# lf.net
KiCad netlist of a schematic drawn in EAGLE
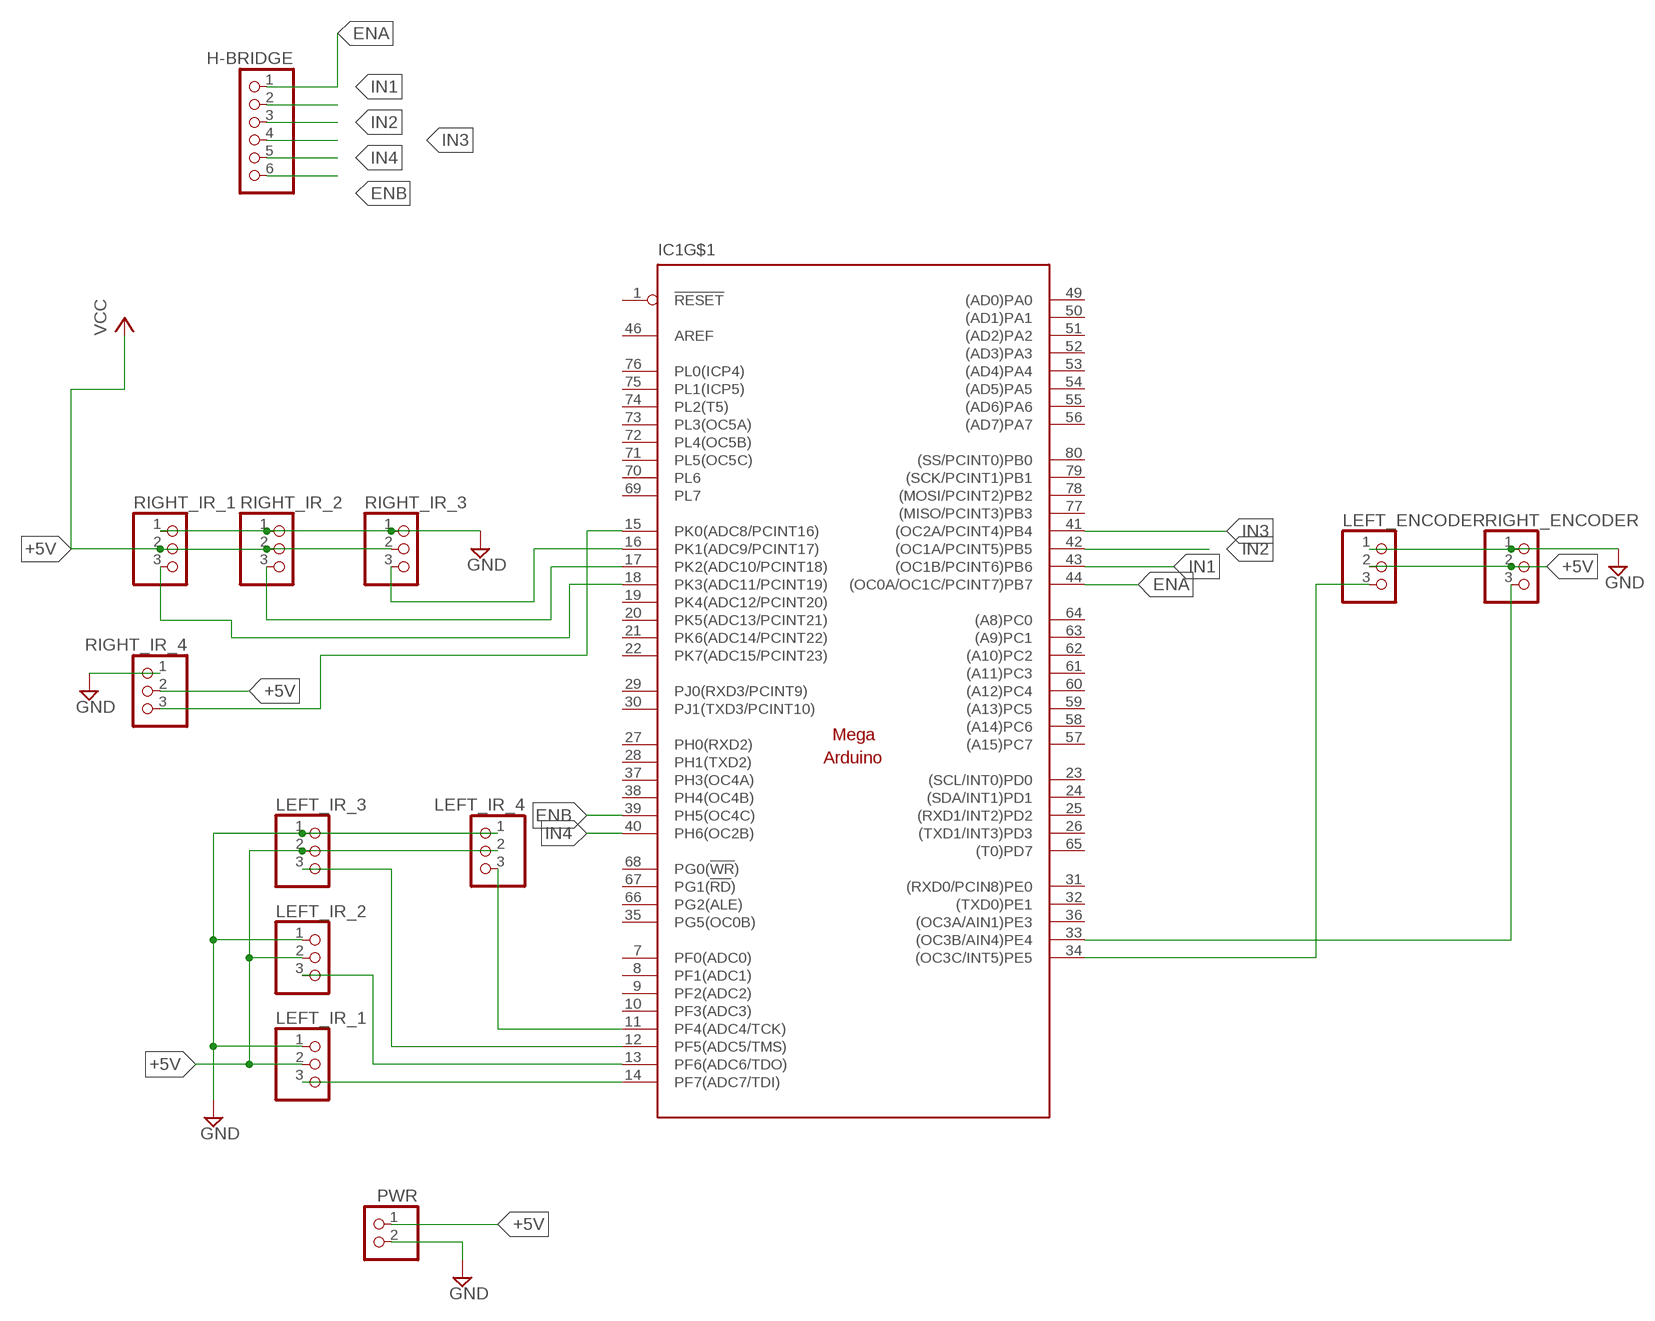
[diagram p0: schematic, sheet 1]

(export (version "E")
  (design (tool "Eeschema 10.0.6"))
  (components
    (comp (ref "H-BRIDGE")
      (value "PINHD-1X6")
      (footprint "eagle-import:1X06")
      (libsource (lib "eagle-import") (part "PINHD-1X6"))
    )
    (comp (ref "IC1")
      (value "MEGAARDUINO_22")
      (footprint "eagle-import:MEGA_ARDUINO_2")
      (libsource (lib "eagle-import") (part "MEGAARDUINO_22"))
    )
    (comp (ref "LEFT_ENCODER")
      (value "PINHD-1X3")
      (footprint "eagle-import:1X03")
      (libsource (lib "eagle-import") (part "PINHD-1X3"))
    )
    (comp (ref "LEFT_IR_1")
      (value "PINHD-1X3")
      (footprint "eagle-import:1X03")
      (libsource (lib "eagle-import") (part "PINHD-1X3"))
    )
    (comp (ref "LEFT_IR_2")
      (value "PINHD-1X3")
      (footprint "eagle-import:1X03")
      (libsource (lib "eagle-import") (part "PINHD-1X3"))
    )
    (comp (ref "LEFT_IR_3")
      (value "PINHD-1X3")
      (footprint "eagle-import:1X03")
      (libsource (lib "eagle-import") (part "PINHD-1X3"))
    )
    (comp (ref "LEFT_IR_4")
      (value "PINHD-1X3")
      (footprint "eagle-import:1X03")
      (libsource (lib "eagle-import") (part "PINHD-1X3"))
    )
    (comp (ref "PWR")
      (value "PINHD-1X2")
      (footprint "eagle-import:1X02")
      (libsource (lib "eagle-import") (part "PINHD-1X2"))
    )
    (comp (ref "RIGHT_ENCODER")
      (value "PINHD-1X3")
      (footprint "eagle-import:1X03")
      (libsource (lib "eagle-import") (part "PINHD-1X3"))
    )
    (comp (ref "RIGHT_IR_1")
      (value "PINHD-1X3")
      (footprint "eagle-import:1X03")
      (libsource (lib "eagle-import") (part "PINHD-1X3"))
    )
    (comp (ref "RIGHT_IR_2")
      (value "PINHD-1X3")
      (footprint "eagle-import:1X03")
      (libsource (lib "eagle-import") (part "PINHD-1X3"))
    )
    (comp (ref "RIGHT_IR_3")
      (value "PINHD-1X3")
      (footprint "eagle-import:1X03")
      (libsource (lib "eagle-import") (part "PINHD-1X3"))
    )
    (comp (ref "RIGHT_IR_4")
      (value "PINHD-1X3")
      (footprint "eagle-import:1X03")
      (libsource (lib "eagle-import") (part "PINHD-1X3"))
    )
  )
  (nets
    (net (code "1") (name "+5V") (class "Default")
      (node (ref "LEFT_ENCODER") (pin "2") (pinfunction "2_2") (pintype "passive"))
      (node (ref "LEFT_IR_1") (pin "2") (pinfunction "2_2") (pintype "passive"))
      (node (ref "LEFT_IR_2") (pin "2") (pinfunction "2_2") (pintype "passive"))
      (node (ref "LEFT_IR_3") (pin "2") (pinfunction "2_2") (pintype "passive"))
      (node (ref "LEFT_IR_4") (pin "2") (pinfunction "2_2") (pintype "passive"))
      (node (ref "PWR") (pin "1") (pinfunction "1_1") (pintype "passive"))
      (node (ref "RIGHT_ENCODER") (pin "2") (pinfunction "2_2") (pintype "passive"))
      (node (ref "RIGHT_IR_1") (pin "2") (pinfunction "2_2") (pintype "passive"))
      (node (ref "RIGHT_IR_2") (pin "2") (pinfunction "2_2") (pintype "passive"))
      (node (ref "RIGHT_IR_3") (pin "2") (pinfunction "2_2") (pintype "passive"))
      (node (ref "RIGHT_IR_4") (pin "2") (pinfunction "2_2") (pintype "passive"))
    )
    (net (code "2") (name "ENA") (class "Default")
      (node (ref "H-BRIDGE") (pin "1") (pinfunction "1_1") (pintype "passive"))
      (node (ref "IC1") (pin "44") (pinfunction "(OC0A/OC1C/PCINT7)PB7_44") (pintype "bidirectional"))
    )
    (net (code "3") (name "ENB") (class "Default")
      (node (ref "H-BRIDGE") (pin "6") (pinfunction "6_6") (pintype "passive"))
      (node (ref "IC1") (pin "39") (pinfunction "PH5(OC4C)_39") (pintype "bidirectional"))
    )
    (net (code "4") (name "GND") (class "Default")
      (node (ref "LEFT_ENCODER") (pin "1") (pinfunction "1_1") (pintype "passive"))
      (node (ref "LEFT_IR_1") (pin "1") (pinfunction "1_1") (pintype "passive"))
      (node (ref "LEFT_IR_2") (pin "1") (pinfunction "1_1") (pintype "passive"))
      (node (ref "LEFT_IR_3") (pin "1") (pinfunction "1_1") (pintype "passive"))
      (node (ref "LEFT_IR_4") (pin "1") (pinfunction "1_1") (pintype "passive"))
      (node (ref "PWR") (pin "2") (pinfunction "2_2") (pintype "passive"))
      (node (ref "RIGHT_ENCODER") (pin "1") (pinfunction "1_1") (pintype "passive"))
      (node (ref "RIGHT_IR_1") (pin "1") (pinfunction "1_1") (pintype "passive"))
      (node (ref "RIGHT_IR_2") (pin "1") (pinfunction "1_1") (pintype "passive"))
      (node (ref "RIGHT_IR_3") (pin "1") (pinfunction "1_1") (pintype "passive"))
      (node (ref "RIGHT_IR_4") (pin "1") (pinfunction "1_1") (pintype "passive"))
    )
    (net (code "5") (name "IN1") (class "Default")
      (node (ref "H-BRIDGE") (pin "2") (pinfunction "2_2") (pintype "passive"))
      (node (ref "IC1") (pin "43") (pinfunction "(OC1B/PCINT6)PB6_43") (pintype "bidirectional"))
    )
    (net (code "6") (name "IN2") (class "Default")
      (node (ref "H-BRIDGE") (pin "3") (pinfunction "3_3") (pintype "passive"))
      (node (ref "IC1") (pin "42") (pinfunction "(OC1A/PCINT5)PB5_42") (pintype "bidirectional"))
    )
    (net (code "7") (name "IN3") (class "Default")
      (node (ref "H-BRIDGE") (pin "4") (pinfunction "4_4") (pintype "passive"))
      (node (ref "IC1") (pin "41") (pinfunction "(OC2A/PCINT4)PB4_41") (pintype "bidirectional"))
    )
    (net (code "8") (name "IN4") (class "Default")
      (node (ref "H-BRIDGE") (pin "5") (pinfunction "5_5") (pintype "passive"))
      (node (ref "IC1") (pin "40") (pinfunction "PH6(OC2B)_40") (pintype "bidirectional"))
    )
    (net (code "9") (name "Net-(IC1A-(OC3B{slash}AIN4)PE4)") (class "Default")
      (node (ref "IC1") (pin "33") (pinfunction "(OC3B/AIN4)PE4_33") (pintype "bidirectional"))
      (node (ref "RIGHT_ENCODER") (pin "3") (pinfunction "3_3") (pintype "passive"))
    )
    (net (code "10") (name "Net-(IC1A-(OC3C{slash}INT5)PE5)") (class "Default")
      (node (ref "IC1") (pin "34") (pinfunction "(OC3C/INT5)PE5_34") (pintype "bidirectional"))
      (node (ref "LEFT_ENCODER") (pin "3") (pinfunction "3_3") (pintype "passive"))
    )
    (net (code "11") (name "Net-(IC1A-PF4(ADC4{slash}TCK))") (class "Default")
      (node (ref "IC1") (pin "11") (pinfunction "PF4(ADC4/TCK)_11") (pintype "bidirectional"))
      (node (ref "LEFT_IR_4") (pin "3") (pinfunction "3_3") (pintype "passive"))
    )
    (net (code "12") (name "Net-(IC1A-PF5(ADC5{slash}TMS))") (class "Default")
      (node (ref "IC1") (pin "12") (pinfunction "PF5(ADC5/TMS)_12") (pintype "bidirectional"))
      (node (ref "LEFT_IR_3") (pin "3") (pinfunction "3_3") (pintype "passive"))
    )
    (net (code "13") (name "Net-(IC1A-PF6(ADC6{slash}TDO))") (class "Default")
      (node (ref "IC1") (pin "13") (pinfunction "PF6(ADC6/TDO)_13") (pintype "bidirectional"))
      (node (ref "LEFT_IR_2") (pin "3") (pinfunction "3_3") (pintype "passive"))
    )
    (net (code "14") (name "Net-(IC1A-PF7(ADC7{slash}TDI))") (class "Default")
      (node (ref "IC1") (pin "14") (pinfunction "PF7(ADC7/TDI)_14") (pintype "bidirectional"))
      (node (ref "LEFT_IR_1") (pin "3") (pinfunction "3_3") (pintype "passive"))
    )
    (net (code "15") (name "Net-(IC1A-PK0(ADC8{slash}PCINT16))") (class "Default")
      (node (ref "IC1") (pin "15") (pinfunction "PK0(ADC8/PCINT16)_15") (pintype "bidirectional"))
      (node (ref "RIGHT_IR_4") (pin "3") (pinfunction "3_3") (pintype "passive"))
    )
    (net (code "16") (name "Net-(IC1A-PK1(ADC9{slash}PCINT17))") (class "Default")
      (node (ref "IC1") (pin "16") (pinfunction "PK1(ADC9/PCINT17)_16") (pintype "bidirectional"))
      (node (ref "RIGHT_IR_3") (pin "3") (pinfunction "3_3") (pintype "passive"))
    )
    (net (code "17") (name "Net-(IC1A-PK2(ADC10{slash}PCINT18))") (class "Default")
      (node (ref "IC1") (pin "17") (pinfunction "PK2(ADC10/PCINT18)_17") (pintype "bidirectional"))
      (node (ref "RIGHT_IR_2") (pin "3") (pinfunction "3_3") (pintype "passive"))
    )
    (net (code "18") (name "Net-(IC1A-PK3(ADC11{slash}PCINT19))") (class "Default")
      (node (ref "IC1") (pin "18") (pinfunction "PK3(ADC11/PCINT19)_18") (pintype "bidirectional"))
      (node (ref "RIGHT_IR_1") (pin "3") (pinfunction "3_3") (pintype "passive"))
    )
    (net (code "19") (name "unconnected-(IC1A-(A8)PC0-Pad64)") (class "Default")
      (node (ref "IC1") (pin "64") (pinfunction "(A8)PC0_64") (pintype "bidirectional"))
    )
    (net (code "20") (name "unconnected-(IC1A-(A9)PC1-Pad63)") (class "Default")
      (node (ref "IC1") (pin "63") (pinfunction "(A9)PC1_63") (pintype "bidirectional"))
    )
    (net (code "21") (name "unconnected-(IC1A-(A10)PC2-Pad62)") (class "Default")
      (node (ref "IC1") (pin "62") (pinfunction "(A10)PC2_62") (pintype "bidirectional"))
    )
    (net (code "22") (name "unconnected-(IC1A-(A11)PC3-Pad61)") (class "Default")
      (node (ref "IC1") (pin "61") (pinfunction "(A11)PC3_61") (pintype "bidirectional"))
    )
    (net (code "23") (name "unconnected-(IC1A-(A12)PC4-Pad60)") (class "Default")
      (node (ref "IC1") (pin "60") (pinfunction "(A12)PC4_60") (pintype "bidirectional"))
    )
    (net (code "24") (name "unconnected-(IC1A-(A13)PC5-Pad59)") (class "Default")
      (node (ref "IC1") (pin "59") (pinfunction "(A13)PC5_59") (pintype "bidirectional"))
    )
    (net (code "25") (name "unconnected-(IC1A-(A14)PC6-Pad58)") (class "Default")
      (node (ref "IC1") (pin "58") (pinfunction "(A14)PC6_58") (pintype "bidirectional"))
    )
    (net (code "26") (name "unconnected-(IC1A-(A15)PC7-Pad57)") (class "Default")
      (node (ref "IC1") (pin "57") (pinfunction "(A15)PC7_57") (pintype "bidirectional"))
    )
    (net (code "27") (name "unconnected-(IC1A-(AD0)PA0-Pad49)") (class "Default")
      (node (ref "IC1") (pin "49") (pinfunction "(AD0)PA0_49") (pintype "bidirectional"))
    )
    (net (code "28") (name "unconnected-(IC1A-(AD1)PA1-Pad50)") (class "Default")
      (node (ref "IC1") (pin "50") (pinfunction "(AD1)PA1_50") (pintype "bidirectional"))
    )
    (net (code "29") (name "unconnected-(IC1A-(AD2)PA2-Pad51)") (class "Default")
      (node (ref "IC1") (pin "51") (pinfunction "(AD2)PA2_51") (pintype "bidirectional"))
    )
    (net (code "30") (name "unconnected-(IC1A-(AD3)PA3-Pad52)") (class "Default")
      (node (ref "IC1") (pin "52") (pinfunction "(AD3)PA3_52") (pintype "bidirectional"))
    )
    (net (code "31") (name "unconnected-(IC1A-(AD4)PA4-Pad53)") (class "Default")
      (node (ref "IC1") (pin "53") (pinfunction "(AD4)PA4_53") (pintype "bidirectional"))
    )
    (net (code "32") (name "unconnected-(IC1A-(AD5)PA5-Pad54)") (class "Default")
      (node (ref "IC1") (pin "54") (pinfunction "(AD5)PA5_54") (pintype "bidirectional"))
    )
    (net (code "33") (name "unconnected-(IC1A-(AD6)PA6-Pad55)") (class "Default")
      (node (ref "IC1") (pin "55") (pinfunction "(AD6)PA6_55") (pintype "bidirectional"))
    )
    (net (code "34") (name "unconnected-(IC1A-(AD7)PA7-Pad56)") (class "Default")
      (node (ref "IC1") (pin "56") (pinfunction "(AD7)PA7_56") (pintype "bidirectional"))
    )
    (net (code "35") (name "unconnected-(IC1A-(MISO{slash}PCINT3)PB3-Pad77)") (class "Default")
      (node (ref "IC1") (pin "77") (pinfunction "(MISO/PCINT3)PB3_77") (pintype "bidirectional"))
    )
    (net (code "36") (name "unconnected-(IC1A-(MOSI{slash}PCINT2)PB2-Pad78)") (class "Default")
      (node (ref "IC1") (pin "78") (pinfunction "(MOSI/PCINT2)PB2_78") (pintype "bidirectional"))
    )
    (net (code "37") (name "unconnected-(IC1A-(OC3A{slash}AIN1)PE3-Pad36)") (class "Default")
      (node (ref "IC1") (pin "36") (pinfunction "(OC3A/AIN1)PE3_36") (pintype "bidirectional"))
    )
    (net (code "38") (name "unconnected-(IC1A-(RXD0{slash}PCIN8)PE0-Pad31)") (class "Default")
      (node (ref "IC1") (pin "31") (pinfunction "(RXD0/PCIN8)PE0_31") (pintype "bidirectional"))
    )
    (net (code "39") (name "unconnected-(IC1A-(RXD1{slash}INT2)PD2-Pad25)") (class "Default")
      (node (ref "IC1") (pin "25") (pinfunction "(RXD1/INT2)PD2_25") (pintype "bidirectional"))
    )
    (net (code "40") (name "unconnected-(IC1A-(SCK{slash}PCINT1)PB1-Pad79)") (class "Default")
      (node (ref "IC1") (pin "79") (pinfunction "(SCK/PCINT1)PB1_79") (pintype "bidirectional"))
    )
    (net (code "41") (name "unconnected-(IC1A-(SCL{slash}INT0)PD0-Pad23)") (class "Default")
      (node (ref "IC1") (pin "23") (pinfunction "(SCL/INT0)PD0_23") (pintype "bidirectional"))
    )
    (net (code "42") (name "unconnected-(IC1A-(SDA{slash}INT1)PD1-Pad24)") (class "Default")
      (node (ref "IC1") (pin "24") (pinfunction "(SDA/INT1)PD1_24") (pintype "bidirectional"))
    )
    (net (code "43") (name "unconnected-(IC1A-(SS{slash}PCINT0)PB0-Pad80)") (class "Default")
      (node (ref "IC1") (pin "80") (pinfunction "(SS/PCINT0)PB0_80") (pintype "bidirectional"))
    )
    (net (code "44") (name "unconnected-(IC1A-(T0)PD7-Pad65)") (class "Default")
      (node (ref "IC1") (pin "65") (pinfunction "(T0)PD7_65") (pintype "bidirectional"))
    )
    (net (code "45") (name "unconnected-(IC1A-(TXD0)PE1-Pad32)") (class "Default")
      (node (ref "IC1") (pin "32") (pinfunction "(TXD0)PE1_32") (pintype "bidirectional"))
    )
    (net (code "46") (name "unconnected-(IC1A-(TXD1{slash}INT3)PD3-Pad26)") (class "Default")
      (node (ref "IC1") (pin "26") (pinfunction "(TXD1/INT3)PD3_26") (pintype "bidirectional"))
    )
    (net (code "47") (name "unconnected-(IC1A-AREF-Pad46)") (class "Default")
      (node (ref "IC1") (pin "46") (pinfunction "AREF_46") (pintype "bidirectional"))
    )
    (net (code "48") (name "unconnected-(IC1A-PF0(ADC0)-Pad7)") (class "Default")
      (node (ref "IC1") (pin "7") (pinfunction "PF0(ADC0)_7") (pintype "bidirectional"))
    )
    (net (code "49") (name "unconnected-(IC1A-PF1(ADC1)-Pad8)") (class "Default")
      (node (ref "IC1") (pin "8") (pinfunction "PF1(ADC1)_8") (pintype "bidirectional"))
    )
    (net (code "50") (name "unconnected-(IC1A-PF2(ADC2)-Pad9)") (class "Default")
      (node (ref "IC1") (pin "9") (pinfunction "PF2(ADC2)_9") (pintype "bidirectional"))
    )
    (net (code "51") (name "unconnected-(IC1A-PF3(ADC3)-Pad10)") (class "Default")
      (node (ref "IC1") (pin "10") (pinfunction "PF3(ADC3)_10") (pintype "bidirectional"))
    )
    (net (code "52") (name "unconnected-(IC1A-PG0(~{WR})-Pad68)") (class "Default")
      (node (ref "IC1") (pin "68") (pinfunction "PG0(~{WR})_68") (pintype "bidirectional"))
    )
    (net (code "53") (name "unconnected-(IC1A-PG1(~{RD})-Pad67)") (class "Default")
      (node (ref "IC1") (pin "67") (pinfunction "PG1(~{RD})_67") (pintype "bidirectional"))
    )
    (net (code "54") (name "unconnected-(IC1A-PG2(ALE)-Pad66)") (class "Default")
      (node (ref "IC1") (pin "66") (pinfunction "PG2(ALE)_66") (pintype "bidirectional"))
    )
    (net (code "55") (name "unconnected-(IC1A-PG5(OC0B)-Pad35)") (class "Default")
      (node (ref "IC1") (pin "35") (pinfunction "PG5(OC0B)_35") (pintype "bidirectional"))
    )
    (net (code "56") (name "unconnected-(IC1A-PH0(RXD2)-Pad27)") (class "Default")
      (node (ref "IC1") (pin "27") (pinfunction "PH0(RXD2)_27") (pintype "bidirectional"))
    )
    (net (code "57") (name "unconnected-(IC1A-PH1(TXD2)-Pad28)") (class "Default")
      (node (ref "IC1") (pin "28") (pinfunction "PH1(TXD2)_28") (pintype "bidirectional"))
    )
    (net (code "58") (name "unconnected-(IC1A-PH3(OC4A)-Pad37)") (class "Default")
      (node (ref "IC1") (pin "37") (pinfunction "PH3(OC4A)_37") (pintype "bidirectional"))
    )
    (net (code "59") (name "unconnected-(IC1A-PH4(OC4B)-Pad38)") (class "Default")
      (node (ref "IC1") (pin "38") (pinfunction "PH4(OC4B)_38") (pintype "bidirectional"))
    )
    (net (code "60") (name "unconnected-(IC1A-PJ0(RXD3{slash}PCINT9)-Pad29)") (class "Default")
      (node (ref "IC1") (pin "29") (pinfunction "PJ0(RXD3/PCINT9)_29") (pintype "bidirectional"))
    )
    (net (code "61") (name "unconnected-(IC1A-PJ1(TXD3{slash}PCINT10)-Pad30)") (class "Default")
      (node (ref "IC1") (pin "30") (pinfunction "PJ1(TXD3/PCINT10)_30") (pintype "bidirectional"))
    )
    (net (code "62") (name "unconnected-(IC1A-PK4(ADC12{slash}PCINT20)-Pad19)") (class "Default")
      (node (ref "IC1") (pin "19") (pinfunction "PK4(ADC12/PCINT20)_19") (pintype "bidirectional"))
    )
    (net (code "63") (name "unconnected-(IC1A-PK5(ADC13{slash}PCINT21)-Pad20)") (class "Default")
      (node (ref "IC1") (pin "20") (pinfunction "PK5(ADC13/PCINT21)_20") (pintype "bidirectional"))
    )
    (net (code "64") (name "unconnected-(IC1A-PK6(ADC14{slash}PCINT22)-Pad21)") (class "Default")
      (node (ref "IC1") (pin "21") (pinfunction "PK6(ADC14/PCINT22)_21") (pintype "bidirectional"))
    )
    (net (code "65") (name "unconnected-(IC1A-PK7(ADC15{slash}PCINT23)-Pad22)") (class "Default")
      (node (ref "IC1") (pin "22") (pinfunction "PK7(ADC15/PCINT23)_22") (pintype "bidirectional"))
    )
    (net (code "66") (name "unconnected-(IC1A-PL0(ICP4)-Pad76)") (class "Default")
      (node (ref "IC1") (pin "76") (pinfunction "PL0(ICP4)_76") (pintype "bidirectional"))
    )
    (net (code "67") (name "unconnected-(IC1A-PL1(ICP5)-Pad75)") (class "Default")
      (node (ref "IC1") (pin "75") (pinfunction "PL1(ICP5)_75") (pintype "bidirectional"))
    )
    (net (code "68") (name "unconnected-(IC1A-PL2(T5)-Pad74)") (class "Default")
      (node (ref "IC1") (pin "74") (pinfunction "PL2(T5)_74") (pintype "bidirectional"))
    )
    (net (code "69") (name "unconnected-(IC1A-PL3(OC5A)-Pad73)") (class "Default")
      (node (ref "IC1") (pin "73") (pinfunction "PL3(OC5A)_73") (pintype "bidirectional"))
    )
    (net (code "70") (name "unconnected-(IC1A-PL4(OC5B)-Pad72)") (class "Default")
      (node (ref "IC1") (pin "72") (pinfunction "PL4(OC5B)_72") (pintype "bidirectional"))
    )
    (net (code "71") (name "unconnected-(IC1A-PL5(OC5C)-Pad71)") (class "Default")
      (node (ref "IC1") (pin "71") (pinfunction "PL5(OC5C)_71") (pintype "bidirectional"))
    )
    (net (code "72") (name "unconnected-(IC1A-PL6-Pad70)") (class "Default")
      (node (ref "IC1") (pin "70") (pinfunction "PL6_70") (pintype "bidirectional"))
    )
    (net (code "73") (name "unconnected-(IC1A-PL7-Pad69)") (class "Default")
      (node (ref "IC1") (pin "69") (pinfunction "PL7_69") (pintype "bidirectional"))
    )
    (net (code "74") (name "unconnected-(IC1A-~{RESET}-Pad1)") (class "Default")
      (node (ref "IC1") (pin "1") (pinfunction "~{RESET}_1") (pintype "bidirectional"))
    )
  )
)
